# dado_dig.net
KiCad netlist of a schematic drawn in EAGLE
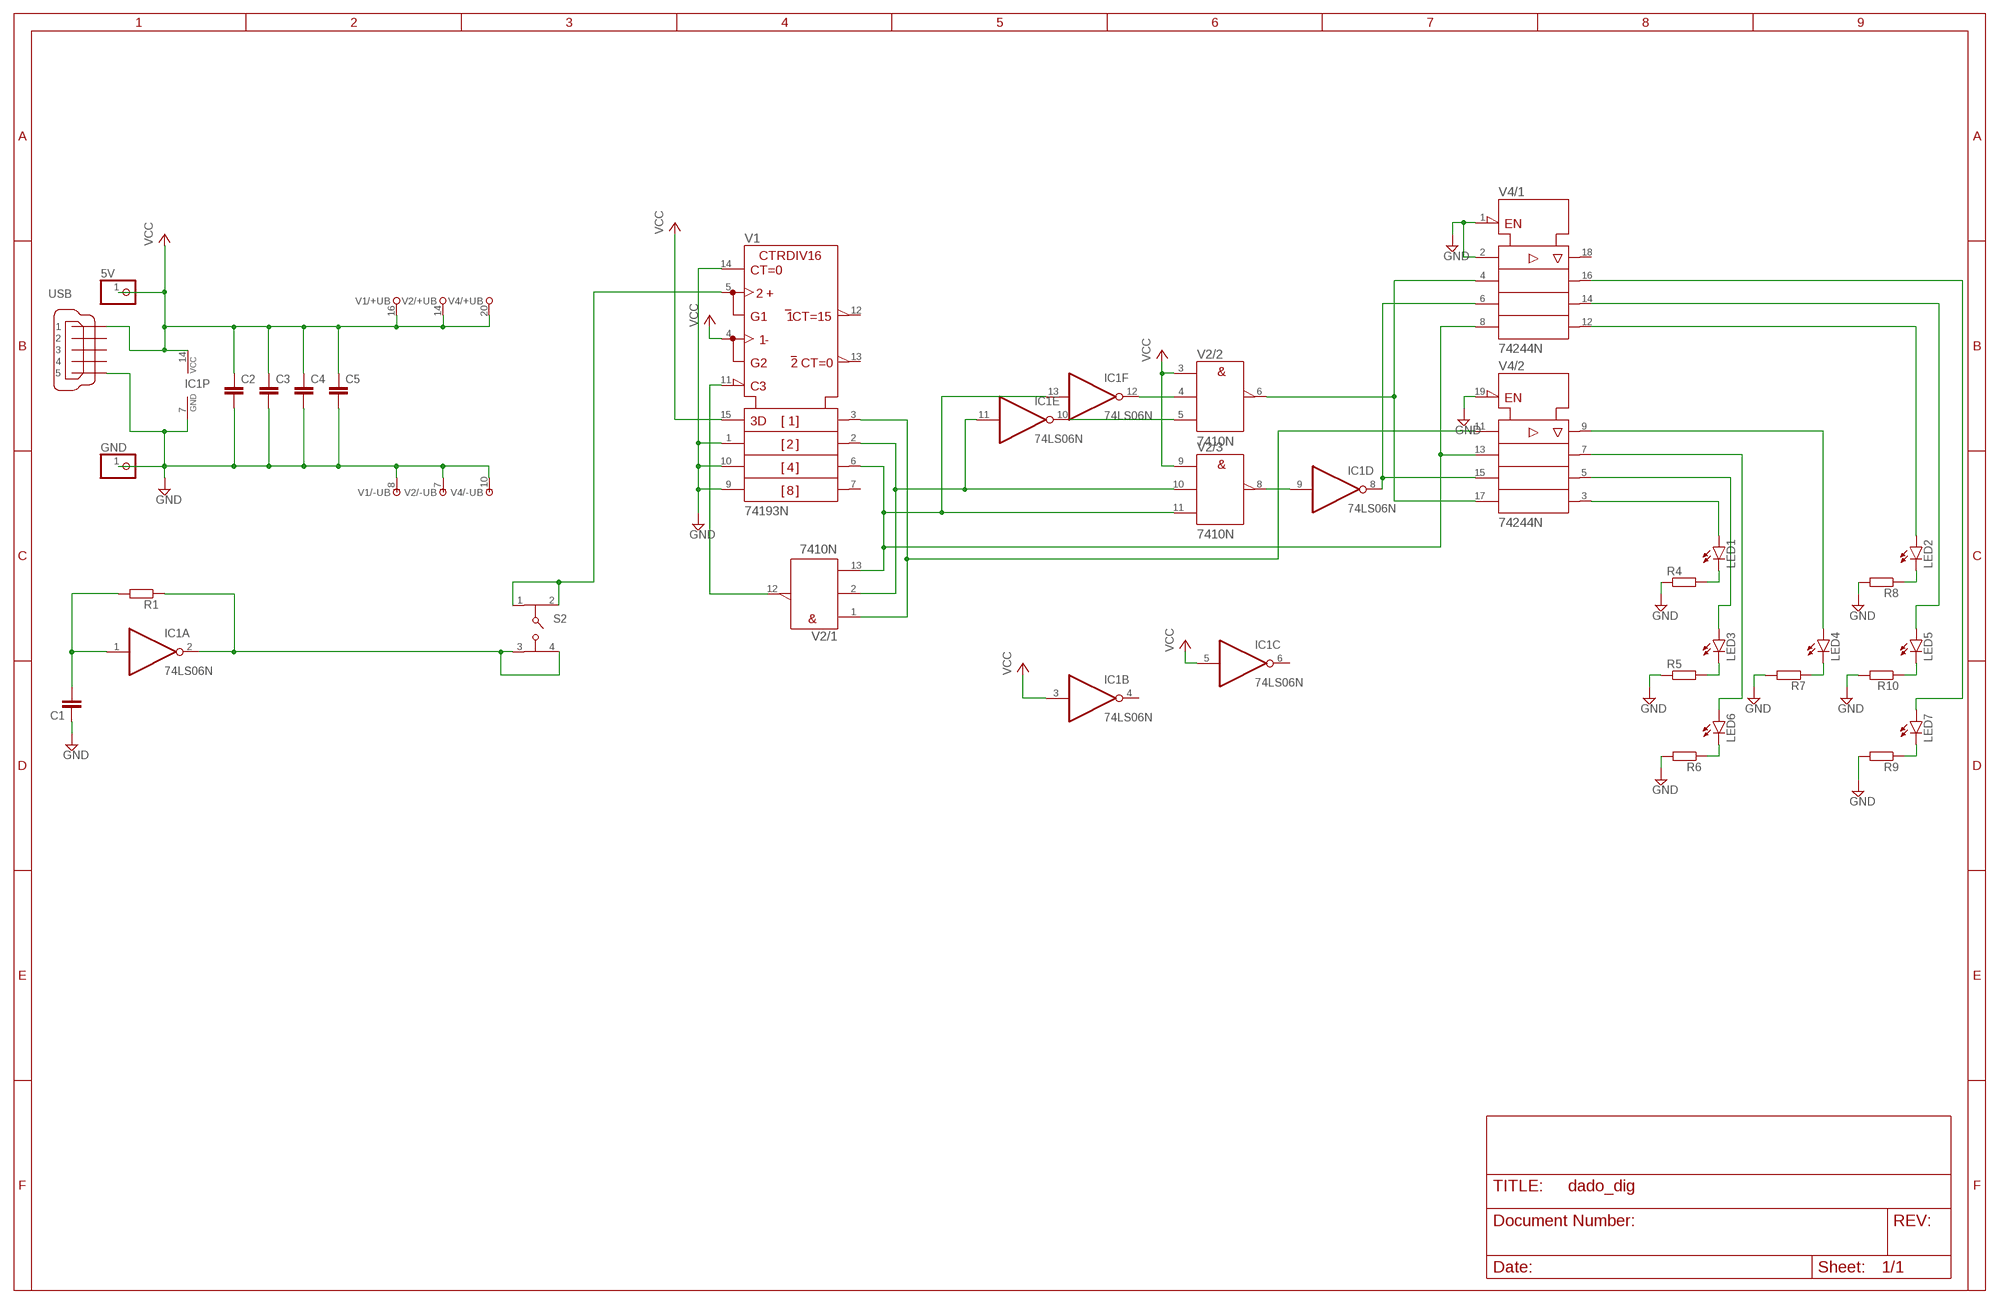
[diagram p0: schematic, sheet 1]

(export (version "E")
  (design (tool "Eeschema 10.0.6"))
  (components
    (comp (ref "5V")
      (value "PINHD-1X1")
      (footprint "eagle-import:1X01")
      (libsource (lib "eagle-import") (part "PINHD-1X1"))
    )
    (comp (ref "C1")
      (value "C-EUC0805K")
      (footprint "eagle-import:C0805K")
      (libsource (lib "eagle-import") (part "C-EUC0805K"))
    )
    (comp (ref "C2")
      (value "C-EUC0805K")
      (footprint "eagle-import:C0805K")
      (libsource (lib "eagle-import") (part "C-EUC0805K"))
    )
    (comp (ref "C3")
      (value "C-EUC0805K")
      (footprint "eagle-import:C0805K")
      (libsource (lib "eagle-import") (part "C-EUC0805K"))
    )
    (comp (ref "C4")
      (value "C-EUC0805K")
      (footprint "eagle-import:C0805K")
      (libsource (lib "eagle-import") (part "C-EUC0805K"))
    )
    (comp (ref "C5")
      (value "C-EUC0805K")
      (footprint "eagle-import:C0805K")
      (libsource (lib "eagle-import") (part "C-EUC0805K"))
    )
    (comp (ref "GND")
      (value "PINHD-1X1")
      (footprint "eagle-import:1X01")
      (libsource (lib "eagle-import") (part "PINHD-1X1"))
    )
    (comp (ref "IC1")
      (value "74LS06N")
      (footprint "eagle-import:DIL14")
      (libsource (lib "eagle-import") (part "7406NLS"))
    )
    (comp (ref "LED1")
      (value "LED5MM")
      (footprint "eagle-import:LED5MM")
      (libsource (lib "eagle-import") (part "LED5MM"))
    )
    (comp (ref "LED2")
      (value "LED5MM")
      (footprint "eagle-import:LED5MM")
      (libsource (lib "eagle-import") (part "LED5MM"))
    )
    (comp (ref "LED3")
      (value "LED5MM")
      (footprint "eagle-import:LED5MM")
      (libsource (lib "eagle-import") (part "LED5MM"))
    )
    (comp (ref "LED4")
      (value "LED5MM")
      (footprint "eagle-import:LED5MM")
      (libsource (lib "eagle-import") (part "LED5MM"))
    )
    (comp (ref "LED5")
      (value "LED5MM")
      (footprint "eagle-import:LED5MM")
      (libsource (lib "eagle-import") (part "LED5MM"))
    )
    (comp (ref "LED6")
      (value "LED5MM")
      (footprint "eagle-import:LED5MM")
      (libsource (lib "eagle-import") (part "LED5MM"))
    )
    (comp (ref "LED7")
      (value "LED5MM")
      (footprint "eagle-import:LED5MM")
      (libsource (lib "eagle-import") (part "LED5MM"))
    )
    (comp (ref "R1")
      (value "R-EU_M0805")
      (footprint "eagle-import:M0805")
      (libsource (lib "eagle-import") (part "R-EU_M0805"))
    )
    (comp (ref "R4")
      (value "R-EU_M0805")
      (footprint "eagle-import:M0805")
      (libsource (lib "eagle-import") (part "R-EU_M0805"))
    )
    (comp (ref "R5")
      (value "R-EU_M0805")
      (footprint "eagle-import:M0805")
      (libsource (lib "eagle-import") (part "R-EU_M0805"))
    )
    (comp (ref "R6")
      (value "R-EU_M0805")
      (footprint "eagle-import:M0805")
      (libsource (lib "eagle-import") (part "R-EU_M0805"))
    )
    (comp (ref "R7")
      (value "R-EU_M0805")
      (footprint "eagle-import:M0805")
      (libsource (lib "eagle-import") (part "R-EU_M0805"))
    )
    (comp (ref "R8")
      (value "R-EU_M0805")
      (footprint "eagle-import:M0805")
      (libsource (lib "eagle-import") (part "R-EU_M0805"))
    )
    (comp (ref "R9")
      (value "R-EU_M0805")
      (footprint "eagle-import:M0805")
      (libsource (lib "eagle-import") (part "R-EU_M0805"))
    )
    (comp (ref "R10")
      (value "R-EU_M0805")
      (footprint "eagle-import:M0805")
      (libsource (lib "eagle-import") (part "R-EU_M0805"))
    )
    (comp (ref "S2")
      (value "430456073736")
      (footprint "eagle-import:430456073736")
      (fields (field (name "MF") "Wurth Electronics"))
      (libsource (lib "eagle-import") (part "430456073736"))
    )
    (comp (ref "USB")
      (value "MINI-USB-32005-301")
      (footprint "eagle-import:32005-301")
      (libsource (lib "eagle-import") (part "MINI-USB-32005-301"))
    )
    (comp (ref "V1")
      (value "74193N")
      (footprint "eagle-import:DIL16")
      (libsource (lib "eagle-import") (part "74193N"))
    )
    (comp (ref "V2")
      (value "7410N")
      (footprint "eagle-import:DIL14")
      (libsource (lib "eagle-import") (part "7410N"))
    )
    (comp (ref "V4")
      (value "74244N")
      (footprint "eagle-import:DIL20")
      (libsource (lib "eagle-import") (part "74244N"))
    )
  )
  (nets
    (net (code "1") (name "GND") (class "Default")
      (node (ref "C1") (pin "1") (pinfunction "1_1") (pintype "passive"))
      (node (ref "C2") (pin "2") (pinfunction "2_2") (pintype "passive"))
      (node (ref "C3") (pin "2") (pinfunction "2_2") (pintype "passive"))
      (node (ref "C4") (pin "2") (pinfunction "2_2") (pintype "passive"))
      (node (ref "C5") (pin "2") (pinfunction "2_2") (pintype "passive"))
      (node (ref "GND") (pin "1") (pinfunction "1_1") (pintype "passive"))
      (node (ref "IC1") (pin "7") (pinfunction "GND_7") (pintype "power_in"))
      (node (ref "R10") (pin "2") (pinfunction "2_2") (pintype "passive"))
      (node (ref "R4") (pin "1") (pinfunction "1_1") (pintype "passive"))
      (node (ref "R5") (pin "1") (pinfunction "1_1") (pintype "passive"))
      (node (ref "R6") (pin "2") (pinfunction "2_2") (pintype "passive"))
      (node (ref "R7") (pin "2") (pinfunction "2_2") (pintype "passive"))
      (node (ref "R8") (pin "2") (pinfunction "2_2") (pintype "passive"))
      (node (ref "R9") (pin "2") (pinfunction "2_2") (pintype "passive"))
      (node (ref "USB") (pin "5") (pinfunction "5_5") (pintype "passive"))
      (node (ref "V1") (pin "1") (pinfunction "B_1") (pintype "input"))
      (node (ref "V1") (pin "10") (pinfunction "C_10") (pintype "input"))
      (node (ref "V1") (pin "14") (pinfunction "CLR_14") (pintype "input"))
      (node (ref "V1") (pin "8") (pinfunction "-UB_8") (pintype "power_in"))
      (node (ref "V1") (pin "9") (pinfunction "D_9") (pintype "input"))
      (node (ref "V2") (pin "7") (pinfunction "-UB_7") (pintype "power_in"))
      (node (ref "V4") (pin "1") (pinfunction "~{G}_1") (pintype "input"))
      (node (ref "V4") (pin "10") (pinfunction "-UB_10") (pintype "power_in"))
      (node (ref "V4") (pin "19") (pinfunction "~{G}_19") (pintype "input"))
      (node (ref "V4") (pin "2") (pinfunction "A1_2") (pintype "input"))
    )
    (net (code "2") (name "Net-(IC1A-I)") (class "Default")
      (node (ref "C1") (pin "2") (pinfunction "2_2") (pintype "passive"))
      (node (ref "IC1") (pin "1") (pinfunction "I_1") (pintype "input"))
      (node (ref "R1") (pin "2") (pinfunction "2_2") (pintype "passive"))
    )
    (net (code "3") (name "Net-(IC1A-O)") (class "Default")
      (node (ref "IC1") (pin "2") (pinfunction "O_2") (pintype "open_collector"))
      (node (ref "R1") (pin "1") (pinfunction "1_1") (pintype "passive"))
      (node (ref "S2") (pin "3") (pinfunction "2_3") (pintype "passive"))
      (node (ref "S2") (pin "4") (pinfunction "4_4") (pintype "passive"))
    )
    (net (code "4") (name "Net-(IC1D-I)") (class "Default")
      (node (ref "IC1") (pin "9") (pinfunction "I_9") (pintype "input"))
      (node (ref "V2") (pin "8") (pinfunction "Y_8") (pintype "output"))
    )
    (net (code "5") (name "Net-(IC1D-O)") (class "Default")
      (node (ref "IC1") (pin "8") (pinfunction "O_8") (pintype "open_collector"))
      (node (ref "V4") (pin "15") (pinfunction "A3_15") (pintype "input"))
      (node (ref "V4") (pin "6") (pinfunction "A3_6") (pintype "input"))
    )
    (net (code "6") (name "Net-(IC1E-I)") (class "Default")
      (node (ref "IC1") (pin "11") (pinfunction "I_11") (pintype "input"))
      (node (ref "V1") (pin "2") (pinfunction "QB_2") (pintype "output"))
      (node (ref "V2") (pin "10") (pinfunction "B_10") (pintype "input"))
      (node (ref "V2") (pin "2") (pinfunction "B_2") (pintype "input"))
    )
    (net (code "7") (name "Net-(IC1E-O)") (class "Default")
      (node (ref "IC1") (pin "10") (pinfunction "O_10") (pintype "open_collector"))
      (node (ref "V2") (pin "5") (pinfunction "C_5") (pintype "input"))
    )
    (net (code "8") (name "Net-(IC1F-I)") (class "Default")
      (node (ref "IC1") (pin "13") (pinfunction "I_13") (pintype "input"))
      (node (ref "V1") (pin "6") (pinfunction "QC_6") (pintype "output"))
      (node (ref "V2") (pin "11") (pinfunction "C_11") (pintype "input"))
      (node (ref "V2") (pin "13") (pinfunction "C_13") (pintype "input"))
      (node (ref "V4") (pin "13") (pinfunction "A2_13") (pintype "input"))
      (node (ref "V4") (pin "8") (pinfunction "A4_8") (pintype "input"))
    )
    (net (code "9") (name "Net-(IC1F-O)") (class "Default")
      (node (ref "IC1") (pin "12") (pinfunction "O_12") (pintype "open_collector"))
      (node (ref "V2") (pin "4") (pinfunction "B_4") (pintype "input"))
    )
    (net (code "10") (name "Net-(LED1-C)") (class "Default")
      (node (ref "LED1") (pin "K") (pinfunction "C_K") (pintype "passive"))
      (node (ref "R4") (pin "2") (pinfunction "2_2") (pintype "passive"))
    )
    (net (code "11") (name "Net-(LED2-C)") (class "Default")
      (node (ref "LED2") (pin "K") (pinfunction "C_K") (pintype "passive"))
      (node (ref "R8") (pin "1") (pinfunction "1_1") (pintype "passive"))
    )
    (net (code "12") (name "Net-(LED3-C)") (class "Default")
      (node (ref "LED3") (pin "K") (pinfunction "C_K") (pintype "passive"))
      (node (ref "R5") (pin "2") (pinfunction "2_2") (pintype "passive"))
    )
    (net (code "13") (name "Net-(LED4-C)") (class "Default")
      (node (ref "LED4") (pin "K") (pinfunction "C_K") (pintype "passive"))
      (node (ref "R7") (pin "1") (pinfunction "1_1") (pintype "passive"))
    )
    (net (code "14") (name "Net-(LED5-C)") (class "Default")
      (node (ref "LED5") (pin "K") (pinfunction "C_K") (pintype "passive"))
      (node (ref "R10") (pin "1") (pinfunction "1_1") (pintype "passive"))
    )
    (net (code "15") (name "Net-(LED6-C)") (class "Default")
      (node (ref "LED6") (pin "K") (pinfunction "C_K") (pintype "passive"))
      (node (ref "R6") (pin "1") (pinfunction "1_1") (pintype "passive"))
    )
    (net (code "16") (name "Net-(LED7-C)") (class "Default")
      (node (ref "LED7") (pin "K") (pinfunction "C_K") (pintype "passive"))
      (node (ref "R9") (pin "1") (pinfunction "1_1") (pintype "passive"))
    )
    (net (code "17") (name "Net-(S2-3)") (class "Default")
      (node (ref "S2") (pin "1") (pinfunction "1_1") (pintype "passive"))
      (node (ref "S2") (pin "2") (pinfunction "3_2") (pintype "passive"))
      (node (ref "V1") (pin "5") (pinfunction "UP_5") (pintype "input"))
    )
    (net (code "18") (name "Net-(V1C-QA)") (class "Default")
      (node (ref "V1") (pin "3") (pinfunction "QA_3") (pintype "output"))
      (node (ref "V2") (pin "1") (pinfunction "A_1") (pintype "input"))
      (node (ref "V4") (pin "11") (pinfunction "A1_11") (pintype "input"))
    )
    (net (code "19") (name "Net-(V1C-~{LOAD})") (class "Default")
      (node (ref "V1") (pin "11") (pinfunction "~{LOAD}_11") (pintype "input"))
      (node (ref "V2") (pin "12") (pinfunction "Y_12") (pintype "output"))
    )
    (net (code "20") (name "Net-(V2D-Y)") (class "Default")
      (node (ref "V2") (pin "6") (pinfunction "Y_6") (pintype "output"))
      (node (ref "V4") (pin "17") (pinfunction "A4_17") (pintype "input"))
      (node (ref "V4") (pin "4") (pinfunction "A2_4") (pintype "input"))
    )
    (net (code "21") (name "Net-(V4C-Y2)") (class "Default")
      (node (ref "LED7") (pin "A") (pinfunction "A_A") (pintype "passive"))
      (node (ref "V4") (pin "16") (pinfunction "Y2_16") (pintype "tri_state"))
    )
    (net (code "22") (name "Net-(V4C-Y3)") (class "Default")
      (node (ref "LED5") (pin "A") (pinfunction "A_A") (pintype "passive"))
      (node (ref "V4") (pin "14") (pinfunction "Y3_14") (pintype "tri_state"))
    )
    (net (code "23") (name "Net-(V4C-Y4)") (class "Default")
      (node (ref "LED2") (pin "A") (pinfunction "A_A") (pintype "passive"))
      (node (ref "V4") (pin "12") (pinfunction "Y4_12") (pintype "tri_state"))
    )
    (net (code "24") (name "Net-(V4D-Y1)") (class "Default")
      (node (ref "LED4") (pin "A") (pinfunction "A_A") (pintype "passive"))
      (node (ref "V4") (pin "9") (pinfunction "Y1_9") (pintype "tri_state"))
    )
    (net (code "25") (name "Net-(V4D-Y2)") (class "Default")
      (node (ref "LED6") (pin "A") (pinfunction "A_A") (pintype "passive"))
      (node (ref "V4") (pin "7") (pinfunction "Y2_7") (pintype "tri_state"))
    )
    (net (code "26") (name "Net-(V4D-Y3)") (class "Default")
      (node (ref "LED3") (pin "A") (pinfunction "A_A") (pintype "passive"))
      (node (ref "V4") (pin "5") (pinfunction "Y3_5") (pintype "tri_state"))
    )
    (net (code "27") (name "Net-(V4D-Y4)") (class "Default")
      (node (ref "LED1") (pin "A") (pinfunction "A_A") (pintype "passive"))
      (node (ref "V4") (pin "3") (pinfunction "Y4_3") (pintype "tri_state"))
    )
    (net (code "28") (name "VCC") (class "Default")
      (node (ref "5V") (pin "1") (pinfunction "1_1") (pintype "passive"))
      (node (ref "C2") (pin "1") (pinfunction "1_1") (pintype "passive"))
      (node (ref "C3") (pin "1") (pinfunction "1_1") (pintype "passive"))
      (node (ref "C4") (pin "1") (pinfunction "1_1") (pintype "passive"))
      (node (ref "C5") (pin "1") (pinfunction "1_1") (pintype "passive"))
      (node (ref "IC1") (pin "14") (pinfunction "VCC_14") (pintype "power_in"))
      (node (ref "IC1") (pin "3") (pinfunction "I_3") (pintype "input"))
      (node (ref "IC1") (pin "5") (pinfunction "I_5") (pintype "input"))
      (node (ref "USB") (pin "1") (pinfunction "1_1") (pintype "passive"))
      (node (ref "V1") (pin "15") (pinfunction "A_15") (pintype "input"))
      (node (ref "V1") (pin "16") (pinfunction "+UB_16") (pintype "power_in"))
      (node (ref "V1") (pin "4") (pinfunction "DOWN_4") (pintype "input"))
      (node (ref "V2") (pin "14") (pinfunction "+UB_14") (pintype "power_in"))
      (node (ref "V2") (pin "3") (pinfunction "A_3") (pintype "input"))
      (node (ref "V2") (pin "9") (pinfunction "A_9") (pintype "input"))
      (node (ref "V4") (pin "20") (pinfunction "+UB_20") (pintype "power_in"))
    )
    (net (code "29") (name "unconnected-(IC1B-O-Pad4)") (class "Default")
      (node (ref "IC1") (pin "4") (pinfunction "O_4") (pintype "open_collector"))
    )
    (net (code "30") (name "unconnected-(IC1C-O-Pad6)") (class "Default")
      (node (ref "IC1") (pin "6") (pinfunction "O_6") (pintype "open_collector"))
    )
    (net (code "31") (name "unconnected-(USB-Pad2)") (class "Default")
      (node (ref "USB") (pin "2") (pinfunction "2_2") (pintype "passive"))
    )
    (net (code "32") (name "unconnected-(USB-Pad3)") (class "Default")
      (node (ref "USB") (pin "3") (pinfunction "3_3") (pintype "passive"))
    )
    (net (code "33") (name "unconnected-(USB-Pad4)") (class "Default")
      (node (ref "USB") (pin "4") (pinfunction "4_4") (pintype "passive"))
    )
    (net (code "34") (name "unconnected-(V1C-QD-Pad7)") (class "Default")
      (node (ref "V1") (pin "7") (pinfunction "QD_7") (pintype "output"))
    )
    (net (code "35") (name "unconnected-(V1C-~{BO}-Pad13)") (class "Default")
      (node (ref "V1") (pin "13") (pinfunction "~{BO}_13") (pintype "output"))
    )
    (net (code "36") (name "unconnected-(V1C-~{CO}-Pad12)") (class "Default")
      (node (ref "V1") (pin "12") (pinfunction "~{CO}_12") (pintype "output"))
    )
    (net (code "37") (name "unconnected-(V4C-Y1-Pad18)") (class "Default")
      (node (ref "V4") (pin "18") (pinfunction "Y1_18") (pintype "tri_state"))
    )
  )
)
